# TK032F8004_TK499.net
KiCad netlist of a schematic drawn in Altium Designer
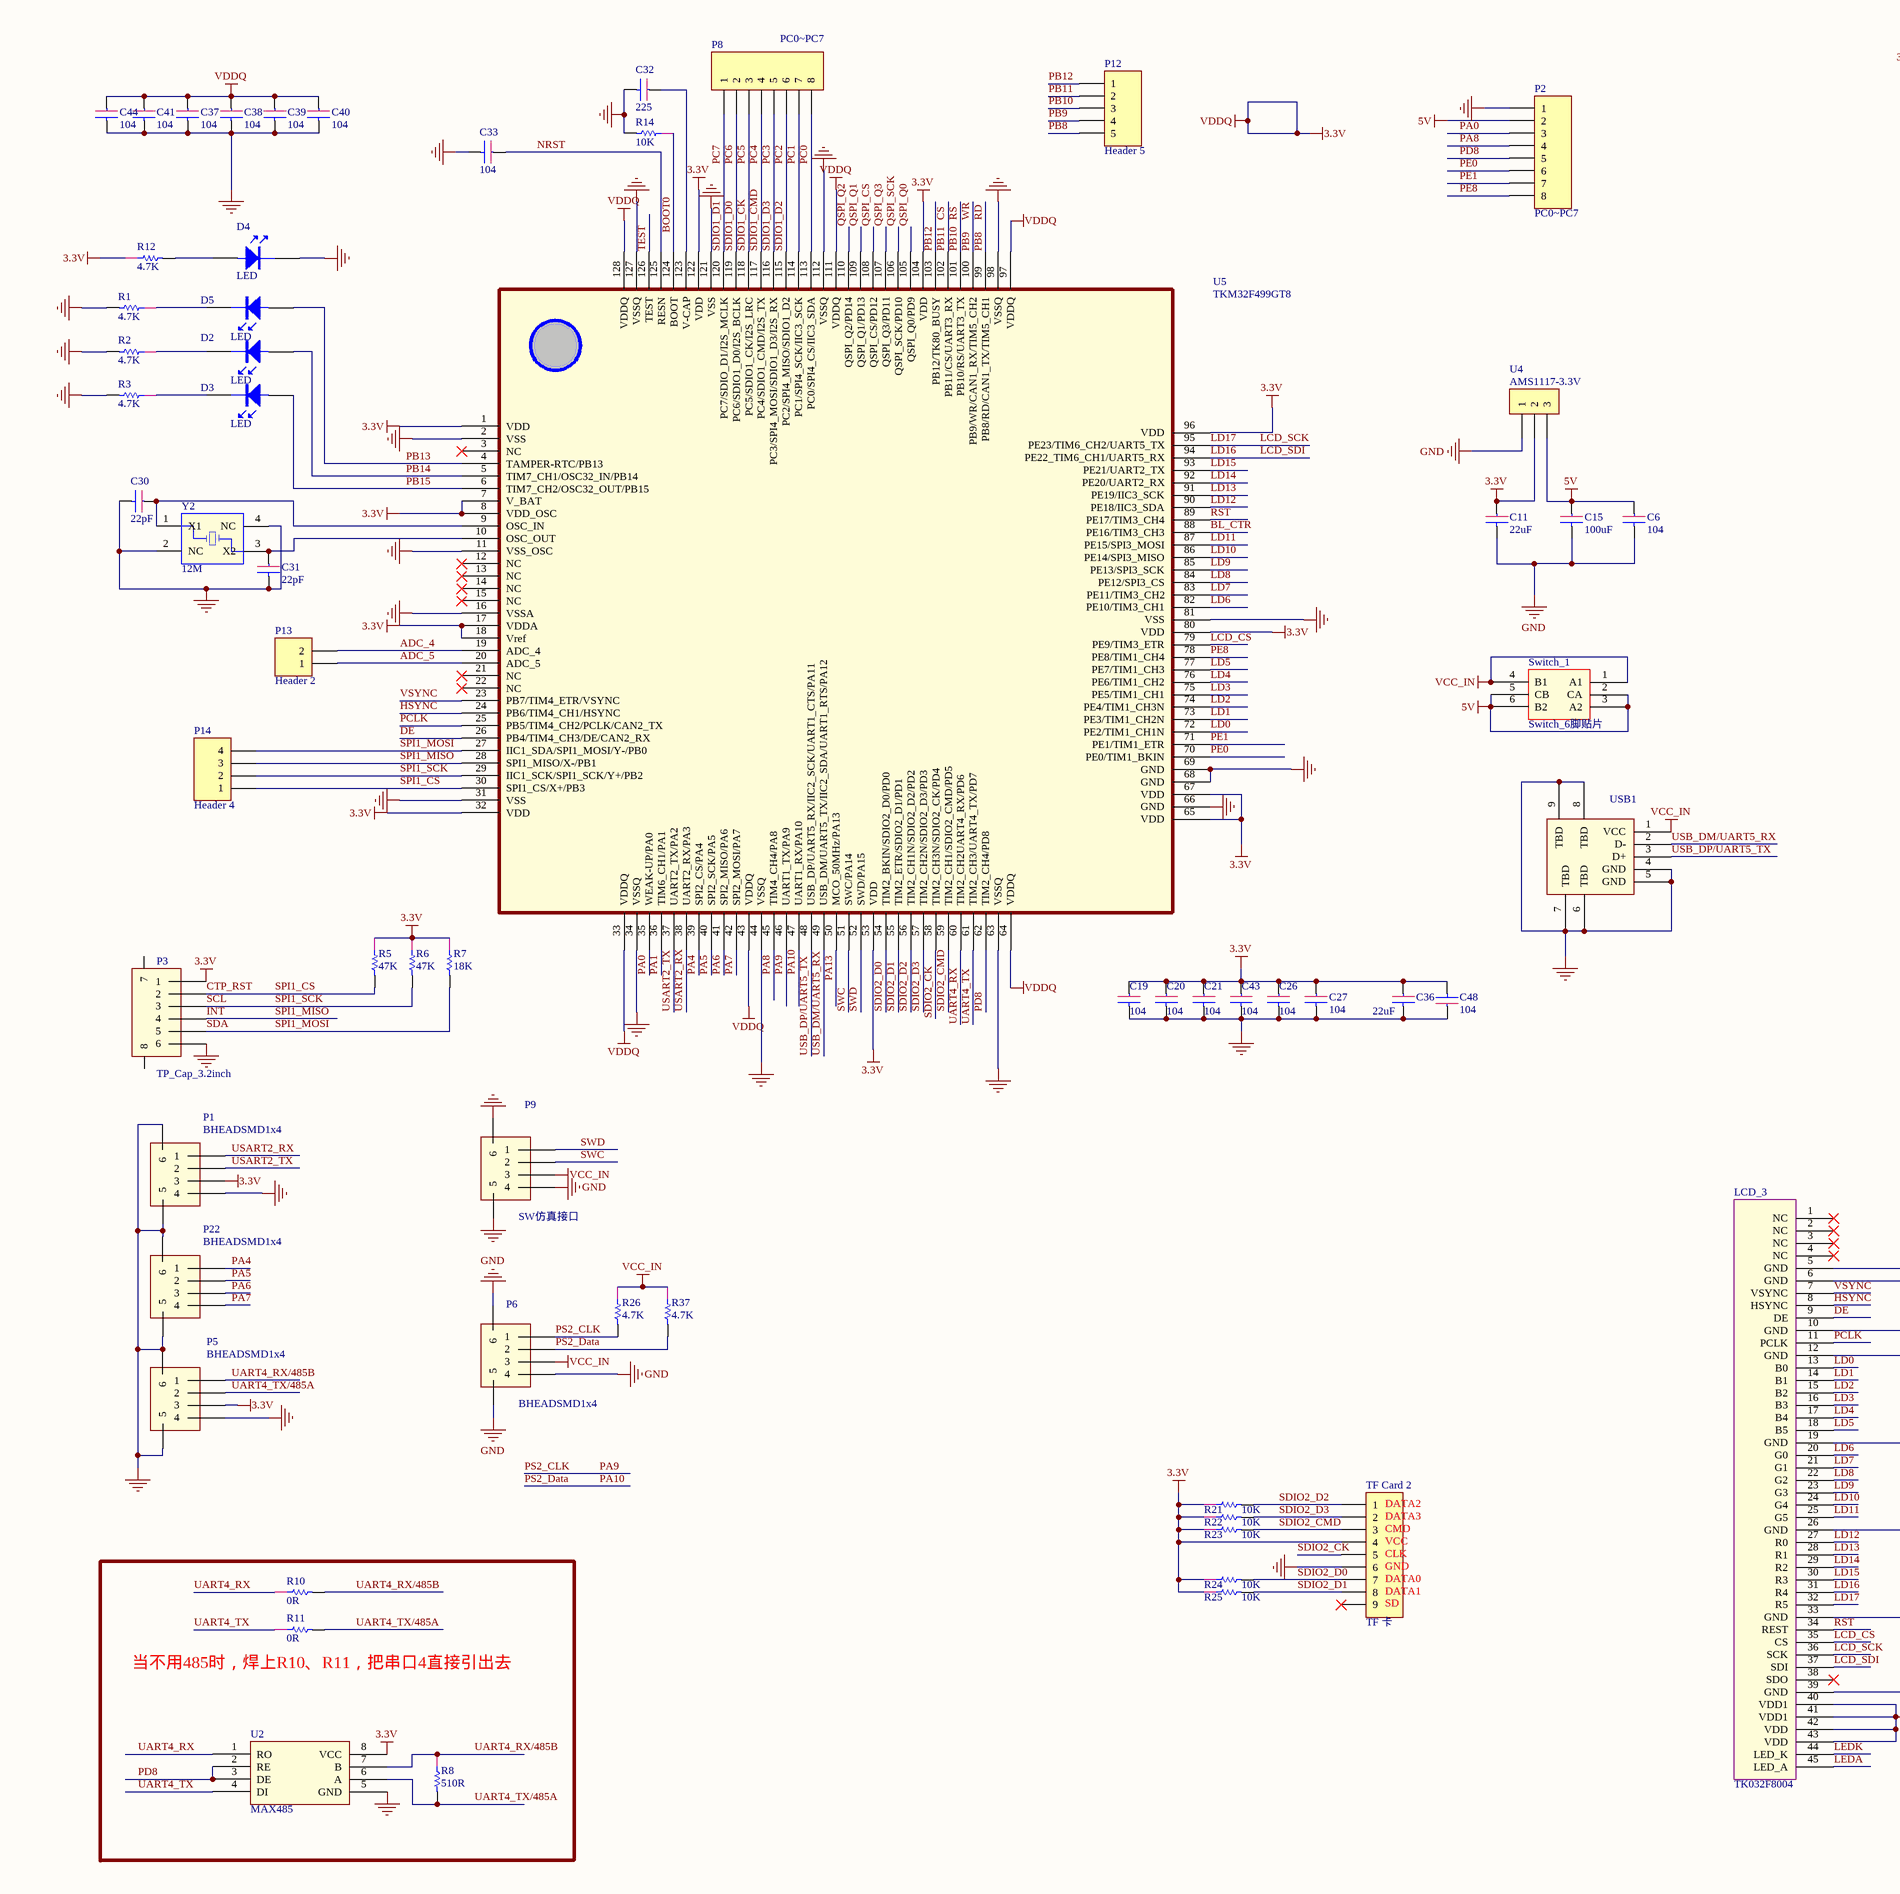
[diagram p0: TK032F8004_TK499.SchDoc, left]
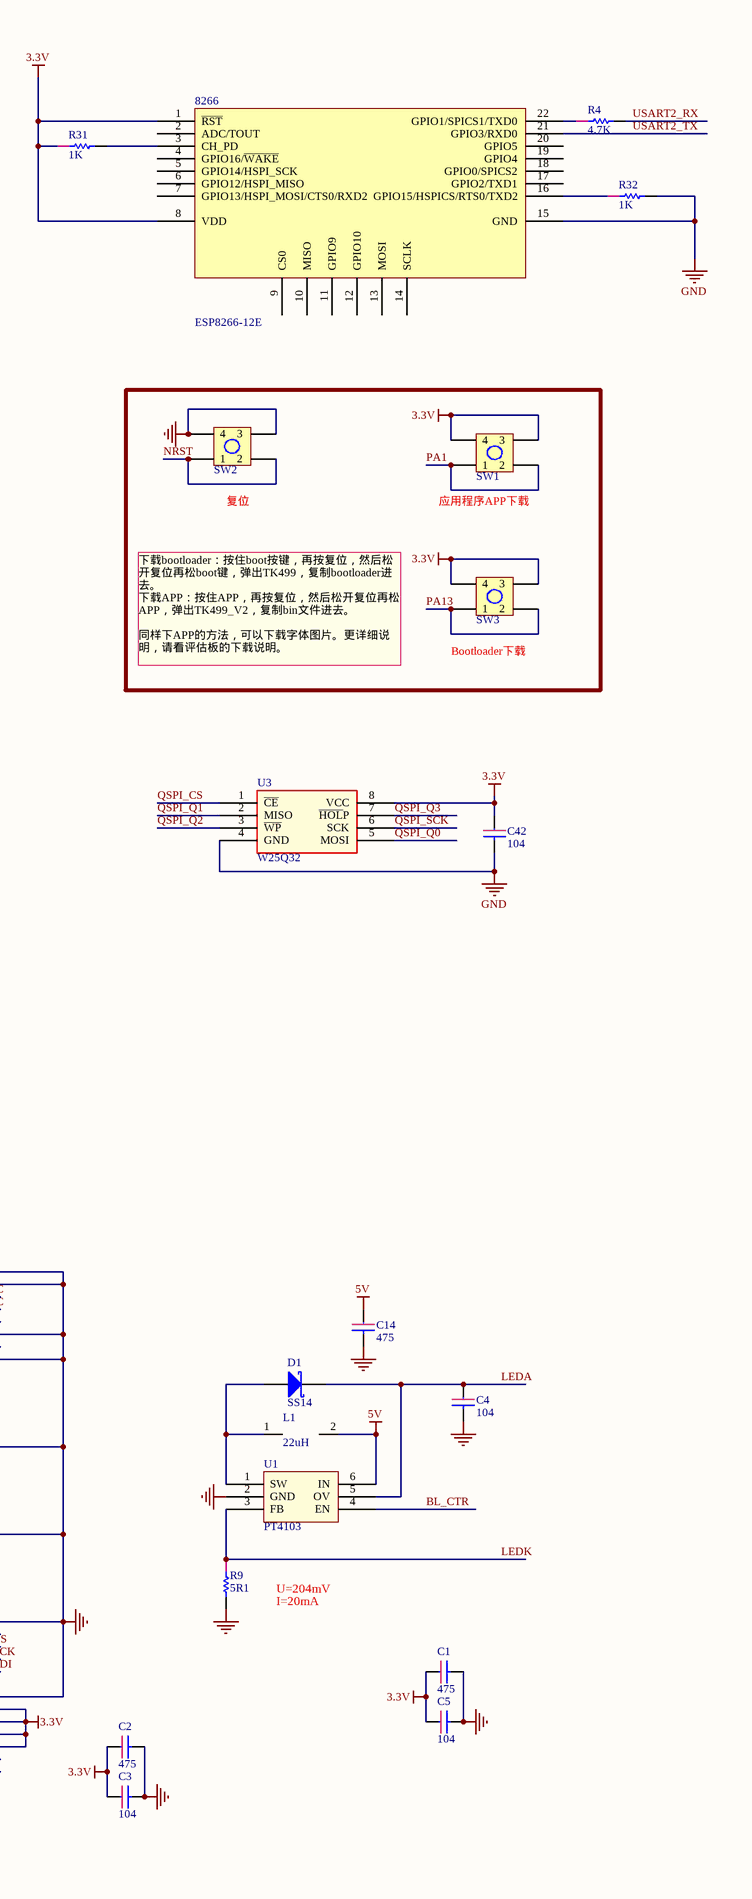
[diagram p1: TK032F8004_TK499.SchDoc, right]

(export (version "E")
  (design (tool "Eeschema 10.0.6"))
  (components
    (comp (ref "8266")
      (value "ESP8266-12E")
      (footprint "ESP8266-12E")
      (libsource (lib "Tiky") (part "ESP8266-12E"))
    )
    (comp (ref "C1") (value "475") (footprint "C0603-2") (libsource (lib "Tiky") (part "cap")))
    (comp (ref "C2") (value "475") (footprint "C0603-2") (libsource (lib "Tiky") (part "cap")))
    (comp (ref "C3") (value "104") (footprint "C0603-1") (libsource (lib "Tiky") (part "cap")))
    (comp (ref "C4") (value "104") (footprint "C0603-2") (libsource (lib "Tiky") (part "cap")))
    (comp (ref "C5") (value "104") (footprint "C0603-1") (libsource (lib "Tiky") (part "cap")))
    (comp (ref "C6") (value "104") (footprint "C0603-1") (libsource (lib "Tiky") (part "cap")))
    (comp (ref "C11") (value "22uF") (footprint "C0805-3") (libsource (lib "Tiky") (part "cap")))
    (comp (ref "C14") (value "475") (footprint "C0603-2") (libsource (lib "Tiky") (part "cap")))
    (comp (ref "C15") (value "100uF") (footprint "Case B 3528") (libsource (lib "Tiky") (part "cap")))
    (comp (ref "C19") (value "104") (footprint "C0603-1") (libsource (lib "Tiky") (part "cap")))
    (comp (ref "C20") (value "104") (footprint "C0603-1") (libsource (lib "Tiky") (part "cap")))
    (comp (ref "C21") (value "104") (footprint "C0603-1") (libsource (lib "Tiky") (part "cap")))
    (comp (ref "C26") (value "104") (footprint "C0603-1") (libsource (lib "Tiky") (part "cap")))
    (comp (ref "C27") (value "104") (footprint "C0603-2") (libsource (lib "Tiky") (part "cap")))
    (comp (ref "C30") (value "22pF") (footprint "C0603-1") (libsource (lib "Tiky") (part "cap")))
    (comp (ref "C31") (value "22pF") (footprint "C0603-1") (libsource (lib "Tiky") (part "cap")))
    (comp (ref "C32") (value "225") (footprint "C0603-2") (libsource (lib "Tiky") (part "cap")))
    (comp (ref "C33") (value "104") (footprint "C0603-1") (libsource (lib "Tiky") (part "cap")))
    (comp (ref "C36") (value "22uF") (footprint "C0805-3") (libsource (lib "Tiky") (part "cap")))
    (comp (ref "C37") (value "104") (footprint "C0603-1") (libsource (lib "Tiky") (part "cap")))
    (comp (ref "C38") (value "104") (footprint "C0603-1") (libsource (lib "Tiky") (part "cap")))
    (comp (ref "C39") (value "104") (footprint "C0603-1") (libsource (lib "Tiky") (part "cap")))
    (comp (ref "C40") (value "104") (footprint "C0603-1") (libsource (lib "Tiky") (part "cap")))
    (comp (ref "C41") (value "104") (footprint "C0603-1") (libsource (lib "Tiky") (part "cap")))
    (comp (ref "C42") (value "104") (footprint "C0603-1") (libsource (lib "Tiky") (part "cap")))
    (comp (ref "C43") (value "104") (footprint "C0603-1") (libsource (lib "Tiky") (part "cap")))
    (comp (ref "C44") (value "104") (footprint "C0603-1") (libsource (lib "Tiky") (part "cap")))
    (comp (ref "C48") (value "104") (footprint "C0603-1") (libsource (lib "Tiky") (part "cap")))
    (comp (ref "D1")
      (value "SS14")
      (footprint "SOD123")
      (description "Schottky Diode")
      (fields (field (name "PUBLISHER") "Altium Limited"))
      (libsource (lib "Miscellaneous Devices") (part "D Schottky"))
    )
    (comp (ref "D2") (value "LED") (footprint "D0603") (libsource (lib "*") (part "LED")))
    (comp (ref "D3") (value "LED") (footprint "D0603") (libsource (lib "*") (part "LED")))
    (comp (ref "D4") (value "LED") (footprint "D0603") (libsource (lib "*") (part "LED")))
    (comp (ref "D5") (value "LED") (footprint "D0603") (libsource (lib "*") (part "LED")))
    (comp (ref "L1") (value "22uH") (footprint "L1206") (libsource (lib "Tiky") (part "Inductor")))
    (comp (ref "LCD_3")
      (value "TK032F8004")
      (footprint "TK032F8004")
      (libsource (lib "Tiky") (part "TK032F8004"))
    )
    (comp (ref "P1")
      (value "BHEADSMD1x4")
      (footprint "BHEADSMD1x4")
      (libsource (lib "Tiky") (part "BHEADSMD1x4"))
    )
    (comp (ref "P2")
      (value "PC0~PC7")
      (footprint "HDR1X8")
      (description "Header, 8-Pin")
      (fields (field (name "PUBLISHER") "Altium Limited"))
      (libsource (lib "Miscellaneous Connectors") (part "Header 8"))
    )
    (comp (ref "P3")
      (value "TP_Cap_3.2inch")
      (footprint "TK032F8004_CTP")
      (libsource (lib "Tiky") (part "BHEADSMD1x6"))
    )
    (comp (ref "P5")
      (value "BHEADSMD1x4")
      (footprint "BHEADSMD1x4")
      (libsource (lib "Tiky") (part "BHEADSMD1x4"))
    )
    (comp (ref "P6")
      (value "BHEADSMD1x4")
      (footprint "BHEADSMD1x4")
      (libsource (lib "Tiky") (part "BHEADSMD1x4"))
    )
    (comp (ref "P8")
      (value "PC0~PC7")
      (footprint "HDR1X8")
      (description "Header, 8-Pin")
      (fields (field (name "PUBLISHER") "Altium Limited"))
      (libsource (lib "") (part "Header 8_1"))
    )
    (comp (ref "P9") (value "SW仿真接口") (footprint "BHEADSMD1x4") (libsource (lib "Tiky") (part "BHEADSMD1x4")))
    (comp (ref "P12")
      (value "Header 5")
      (footprint "HDR1X5")
      (description "Header, 5-Pin")
      (fields (field (name "PUBLISHER") "Altium Limited"))
      (libsource (lib "Miscellaneous Connectors") (part "Header 5"))
    )
    (comp (ref "P13")
      (value "Header 2")
      (footprint "HDR1X2")
      (description "Header, 2-Pin")
      (fields (field (name "PUBLISHER") "Altium Limited"))
      (libsource (lib "Miscellaneous Connectors") (part "Header 2"))
    )
    (comp (ref "P14")
      (value "Header 4")
      (footprint "BHEADSMD1x4")
      (description "Header, 4-Pin")
      (fields (field (name "PUBLISHER") "Altium Limited"))
      (libsource (lib "Miscellaneous Connectors") (part "Header 4"))
    )
    (comp (ref "P22")
      (value "BHEADSMD1x4")
      (footprint "BHEADSMD1x4")
      (libsource (lib "Tiky") (part "BHEADSMD1x4"))
    )
    (comp (ref "R1") (value "4.7K") (footprint "R0603") (libsource (lib "Tiky") (part "Resistor")))
    (comp (ref "R2") (value "4.7K") (footprint "R0603") (libsource (lib "Tiky") (part "Resistor")))
    (comp (ref "R3") (value "4.7K") (footprint "R0603") (libsource (lib "Tiky") (part "Resistor")))
    (comp (ref "R4") (value "4.7K") (footprint "R0603") (libsource (lib "Tiky") (part "Resistor")))
    (comp (ref "R5") (value "47K") (footprint "R0603") (libsource (lib "Tiky") (part "Resistor")))
    (comp (ref "R6") (value "47K") (footprint "R0603") (libsource (lib "Tiky") (part "Resistor")))
    (comp (ref "R7") (value "18K") (footprint "R0603") (libsource (lib "Tiky") (part "Resistor")))
    (comp (ref "R8") (value "510R") (footprint "R0603") (libsource (lib "Tiky") (part "Resistor")))
    (comp (ref "R9") (value "5R1") (footprint "R0603") (libsource (lib "Tiky") (part "Resistor")))
    (comp (ref "R10") (value "0R") (footprint "R0603") (libsource (lib "Tiky") (part "Resistor")))
    (comp (ref "R11") (value "0R") (footprint "R0603") (libsource (lib "Tiky") (part "Resistor")))
    (comp (ref "R12") (value "4.7K") (footprint "R0603") (libsource (lib "Tiky") (part "Resistor")))
    (comp (ref "R14") (value "10K") (footprint "R0603") (libsource (lib "Tiky") (part "Resistor")))
    (comp (ref "R21") (value "10K") (footprint "R0603") (libsource (lib "Tiky") (part "Resistor")))
    (comp (ref "R22") (value "10K") (footprint "R0603") (libsource (lib "Tiky") (part "Resistor")))
    (comp (ref "R23") (value "10K") (footprint "R0603") (libsource (lib "Tiky") (part "Resistor")))
    (comp (ref "R24") (value "10K") (footprint "R0603") (libsource (lib "Tiky") (part "Resistor")))
    (comp (ref "R25") (value "10K") (footprint "R0603") (libsource (lib "Tiky") (part "Resistor")))
    (comp (ref "R26") (value "4.7K") (footprint "R0603") (libsource (lib "Tiky") (part "Resistor")))
    (comp (ref "R31") (value "1K") (footprint "R0603") (libsource (lib "Tiky") (part "Resistor")))
    (comp (ref "R32") (value "1K") (footprint "R0603") (libsource (lib "Tiky") (part "Resistor")))
    (comp (ref "R37") (value "4.7K") (footprint "R0603") (libsource (lib "Tiky") (part "Resistor")))
    (comp (ref "SW1") (value "SW") (footprint "SW") (libsource (lib "Tiky") (part "SW")))
    (comp (ref "SW2") (value "SW") (footprint "SW") (libsource (lib "Tiky") (part "SW")))
    (comp (ref "SW3") (value "SW") (footprint "SW") (libsource (lib "Tiky") (part "SW")))
    (comp (ref "Switch_1")
      (value "Switch_6脚贴片")
      (footprint "Switch_6脚贴片")
      (libsource (lib "Tiky") (part "Switch_6脚贴片"))
    )
    (comp (ref "TF Card 2")
      (value "TF 卡")
      (footprint "Micro_SD")
      (description "Header, 9-Pin")
      (fields (field (name "PUBLISHER") "Altium Limited"))
      (libsource (lib "Miscellaneous Connectors") (part "Header 9"))
    )
    (comp (ref "U1") (value "PT4103") (footprint "SOT23-6") (libsource (lib "Tiky") (part "PT4101")))
    (comp (ref "U2") (value "MAX485") (footprint "SOP8-150") (libsource (lib "Tiky") (part "MAX485")))
    (comp (ref "U3") (value "W25Q32") (footprint "SOP8-215-50") (libsource (lib "Tiky") (part "W25Q16")))
    (comp (ref "U4")
      (value "AMS1117-3.3V")
      (footprint "SOT-223")
      (description "Connector")
      (libsource (lib "Miscellaneous Devices") (part "CON3"))
    )
    (comp (ref "U5")
      (value "TKM32F499GT8")
      (footprint "LQFP128")
      (libsource (lib "Tiky") (part "TKM32F499GT8"))
    )
    (comp (ref "USB1")
      (value "Micro USB")
      (footprint "MicroUSB_带定位柱")
      (libsource (lib "Tiky") (part "Mini USB"))
    )
    (comp (ref "Y2") (value "12M") (footprint "X3225") (libsource (lib "Tiky") (part "晶振_无源_4PIN_SMD")))
  )
  (nets
    (net (code "1") (name "/ADC_4") (class "Default")
      (node (ref "P13") (pin "2") (pinfunction "2_2") (pintype "passive"))
      (node (ref "U5") (pin "19") (pinfunction "ADC_4_19") (pintype "passive"))
    )
    (net (code "2") (name "/ADC_5") (class "Default")
      (node (ref "P13") (pin "1") (pinfunction "1_1") (pintype "passive"))
      (node (ref "U5") (pin "20") (pinfunction "ADC_5_20") (pintype "passive"))
    )
    (net (code "3") (name "/BL_CTR") (class "Default")
      (node (ref "U1") (pin "4") (pinfunction "EN_4") (pintype "passive"))
      (node (ref "U5") (pin "88") (pinfunction "PE16/TIM3_CH3_88") (pintype "passive"))
    )
    (net (code "4") (name "/BOOT0") (class "Default")
      (node (ref "R14") (pin "1") (pinfunction "1_1") (pintype "passive"))
      (node (ref "U5") (pin "124") (pinfunction "BOOT_124") (pintype "passive"))
    )
    (net (code "5") (name "/CS") (class "Default")
      (node (ref "P12") (pin "2") (pinfunction "2_2") (pintype "passive"))
      (node (ref "U5") (pin "102") (pinfunction "PB11/CS/UART3_RX_102") (pintype "passive"))
    )
    (net (code "6") (name "/CTP_RST") (class "Default")
      (node (ref "P14") (pin "1") (pinfunction "1_1") (pintype "passive"))
      (node (ref "P3") (pin "2") (pinfunction "2_2") (pintype "passive"))
      (node (ref "R5") (pin "2") (pinfunction "2_2") (pintype "passive"))
      (node (ref "U5") (pin "30") (pinfunction "SPI1_CS/X+/PB3_30") (pintype "passive"))
    )
    (net (code "7") (name "/DE") (class "Default")
      (node (ref "LCD_3") (pin "9") (pinfunction "DE_9") (pintype "passive"))
      (node (ref "U5") (pin "26") (pinfunction "PB4/TIM4_CH3/DE/CAN2_RX_26") (pintype "passive"))
    )
    (net (code "8") (name "/HSYNC") (class "Default")
      (node (ref "LCD_3") (pin "8") (pinfunction "HSYNC_8") (pintype "passive"))
      (node (ref "U5") (pin "24") (pinfunction "PB6/TIM4_CH1/HSYNC_24") (pintype "passive"))
    )
    (net (code "9") (name "/INT") (class "Default")
      (node (ref "P14") (pin "3") (pinfunction "3_3") (pintype "passive"))
      (node (ref "P3") (pin "4") (pinfunction "4_4") (pintype "passive"))
      (node (ref "U5") (pin "28") (pinfunction "SPI1_MISO/X-/PB1_28") (pintype "passive"))
    )
    (net (code "10") (name "/LCD_CS") (class "Default")
      (node (ref "LCD_3") (pin "35") (pinfunction "CS_35") (pintype "passive"))
      (node (ref "U5") (pin "79") (pinfunction "PE9/TIM3_ETR_79") (pintype "passive"))
    )
    (net (code "11") (name "/LCD_SCK") (class "Default")
      (node (ref "LCD_3") (pin "32") (pinfunction "R5_32") (pintype "passive"))
      (node (ref "LCD_3") (pin "36") (pinfunction "SCK_36") (pintype "passive"))
      (node (ref "U5") (pin "95") (pinfunction "PE23/TIM6_CH2/UART5_TX_95") (pintype "passive"))
    )
    (net (code "12") (name "/LCD_SDI") (class "Default")
      (node (ref "LCD_3") (pin "31") (pinfunction "R4_31") (pintype "passive"))
      (node (ref "LCD_3") (pin "37") (pinfunction "SDI_37") (pintype "passive"))
      (node (ref "U5") (pin "94") (pinfunction "PE22_TIM6_CH1/UART5_RX_94") (pintype "passive"))
    )
    (net (code "13") (name "/LD0") (class "Default")
      (node (ref "LCD_3") (pin "13") (pinfunction "B0_13") (pintype "passive"))
      (node (ref "U5") (pin "72") (pinfunction "PE2/TIM1_CH1N_72") (pintype "passive"))
    )
    (net (code "14") (name "/LD1") (class "Default")
      (node (ref "LCD_3") (pin "14") (pinfunction "B1_14") (pintype "passive"))
      (node (ref "U5") (pin "73") (pinfunction "PE3/TIM1_CH2N_73") (pintype "passive"))
    )
    (net (code "15") (name "/LD2") (class "Default")
      (node (ref "LCD_3") (pin "15") (pinfunction "B2_15") (pintype "passive"))
      (node (ref "U5") (pin "74") (pinfunction "PE4/TIM1_CH3N_74") (pintype "passive"))
    )
    (net (code "16") (name "/LD3") (class "Default")
      (node (ref "LCD_3") (pin "16") (pinfunction "B3_16") (pintype "passive"))
      (node (ref "U5") (pin "75") (pinfunction "PE5/TIM1_CH1_75") (pintype "passive"))
    )
    (net (code "17") (name "/LD4") (class "Default")
      (node (ref "LCD_3") (pin "17") (pinfunction "B4_17") (pintype "passive"))
      (node (ref "U5") (pin "76") (pinfunction "PE6/TIM1_CH2_76") (pintype "passive"))
    )
    (net (code "18") (name "/LD5") (class "Default")
      (node (ref "LCD_3") (pin "18") (pinfunction "B5_18") (pintype "passive"))
      (node (ref "U5") (pin "77") (pinfunction "PE7/TIM1_CH3_77") (pintype "passive"))
    )
    (net (code "19") (name "/LD6") (class "Default")
      (node (ref "LCD_3") (pin "20") (pinfunction "G0_20") (pintype "passive"))
      (node (ref "U5") (pin "82") (pinfunction "PE10/TIM3_CH1_82") (pintype "passive"))
    )
    (net (code "20") (name "/LD7") (class "Default")
      (node (ref "LCD_3") (pin "21") (pinfunction "G1_21") (pintype "passive"))
      (node (ref "U5") (pin "83") (pinfunction "PE11/TIM3_CH2_83") (pintype "passive"))
    )
    (net (code "21") (name "/LD8") (class "Default")
      (node (ref "LCD_3") (pin "22") (pinfunction "G2_22") (pintype "passive"))
      (node (ref "U5") (pin "84") (pinfunction "PE12/SPI3_CS_84") (pintype "passive"))
    )
    (net (code "22") (name "/LD9") (class "Default")
      (node (ref "LCD_3") (pin "23") (pinfunction "G3_23") (pintype "passive"))
      (node (ref "U5") (pin "85") (pinfunction "PE13/SPI3_SCK_85") (pintype "passive"))
    )
    (net (code "23") (name "/LD10") (class "Default")
      (node (ref "LCD_3") (pin "24") (pinfunction "G4_24") (pintype "passive"))
      (node (ref "U5") (pin "86") (pinfunction "PE14/SPI3_MISO_86") (pintype "passive"))
    )
    (net (code "24") (name "/LD11") (class "Default")
      (node (ref "LCD_3") (pin "25") (pinfunction "G5_25") (pintype "passive"))
      (node (ref "U5") (pin "87") (pinfunction "PE15/SPI3_MOSI_87") (pintype "passive"))
    )
    (net (code "25") (name "/LD12") (class "Default")
      (node (ref "LCD_3") (pin "27") (pinfunction "R0_27") (pintype "passive"))
      (node (ref "U5") (pin "90") (pinfunction "PE18/IIC3_SDA_90") (pintype "passive"))
    )
    (net (code "26") (name "/LD13") (class "Default")
      (node (ref "LCD_3") (pin "28") (pinfunction "R1_28") (pintype "passive"))
      (node (ref "U5") (pin "91") (pinfunction "PE19/IIC3_SCK_91") (pintype "passive"))
    )
    (net (code "27") (name "/LD14") (class "Default")
      (node (ref "LCD_3") (pin "29") (pinfunction "R2_29") (pintype "passive"))
      (node (ref "U5") (pin "92") (pinfunction "PE20/UART2_RX_92") (pintype "passive"))
    )
    (net (code "28") (name "/LD15") (class "Default")
      (node (ref "LCD_3") (pin "30") (pinfunction "R3_30") (pintype "passive"))
      (node (ref "U5") (pin "93") (pinfunction "PE21/UART2_TX_93") (pintype "passive"))
    )
    (net (code "29") (name "/LEDA") (class "Default")
      (node (ref "C4") (pin "1") (pinfunction "1_1") (pintype "passive"))
      (node (ref "D1") (pin "2") (pinfunction "K_2") (pintype "passive"))
      (node (ref "LCD_3") (pin "45") (pinfunction "LED_A_45") (pintype "passive"))
      (node (ref "U1") (pin "5") (pinfunction "OV_5") (pintype "passive"))
    )
    (net (code "30") (name "/LEDK") (class "Default")
      (node (ref "LCD_3") (pin "44") (pinfunction "LED_K_44") (pintype "passive"))
      (node (ref "R9") (pin "1") (pinfunction "1_1") (pintype "passive"))
      (node (ref "U1") (pin "3") (pinfunction "FB_3") (pintype "passive"))
    )
    (net (code "31") (name "/NRST") (class "Default")
      (node (ref "C33") (pin "1") (pinfunction "1_1") (pintype "passive"))
      (node (ref "SW2") (pin "1") (pinfunction "1_1") (pintype "passive"))
      (node (ref "SW2") (pin "2") (pinfunction "2_2") (pintype "passive"))
      (node (ref "U5") (pin "125") (pinfunction "RESN_125") (pintype "passive"))
    )
    (net (code "32") (name "/PA0") (class "Default")
      (node (ref "P2") (pin "3") (pinfunction "3_3") (pintype "passive"))
      (node (ref "U5") (pin "35") (pinfunction "WEAK-UP/PA0_35") (pintype "passive"))
    )
    (net (code "33") (name "/PA1") (class "Default")
      (node (ref "SW1") (pin "1") (pinfunction "1_1") (pintype "passive"))
      (node (ref "SW1") (pin "2") (pinfunction "2_2") (pintype "passive"))
      (node (ref "U5") (pin "36") (pinfunction "TIM6_CH1/PA1_36") (pintype "passive"))
    )
    (net (code "34") (name "/PA4") (class "Default")
      (node (ref "P22") (pin "1") (pinfunction "1_1") (pintype "passive"))
      (node (ref "U5") (pin "39") (pinfunction "SPI2_CS/PA4_39") (pintype "passive"))
    )
    (net (code "35") (name "/PA5") (class "Default")
      (node (ref "P22") (pin "2") (pinfunction "2_2") (pintype "passive"))
      (node (ref "U5") (pin "40") (pinfunction "SPI2_SCK/PA5_40") (pintype "passive"))
    )
    (net (code "36") (name "/PA6") (class "Default")
      (node (ref "P22") (pin "3") (pinfunction "3_3") (pintype "passive"))
      (node (ref "U5") (pin "41") (pinfunction "SPI2_MISO/PA6_41") (pintype "passive"))
    )
    (net (code "37") (name "/PA7") (class "Default")
      (node (ref "P22") (pin "4") (pinfunction "4_4") (pintype "passive"))
      (node (ref "U5") (pin "42") (pinfunction "SPI2_MOSI/PA7_42") (pintype "passive"))
    )
    (net (code "38") (name "/PA8") (class "Default")
      (node (ref "P2") (pin "4") (pinfunction "4_4") (pintype "passive"))
      (node (ref "U5") (pin "45") (pinfunction "TIM4_CH4/PA8_45") (pintype "passive"))
    )
    (net (code "39") (name "/PA9") (class "Default")
      (node (ref "P6") (pin "1") (pinfunction "1_1") (pintype "passive"))
      (node (ref "R26") (pin "2") (pinfunction "2_2") (pintype "passive"))
      (node (ref "U5") (pin "46") (pinfunction "UART1_TX/PA9_46") (pintype "passive"))
    )
    (net (code "40") (name "/PA10") (class "Default")
      (node (ref "P6") (pin "2") (pinfunction "2_2") (pintype "passive"))
      (node (ref "R37") (pin "2") (pinfunction "2_2") (pintype "passive"))
      (node (ref "U5") (pin "47") (pinfunction "UART1_RX/PA10_47") (pintype "passive"))
    )
    (net (code "41") (name "/PA13") (class "Default")
      (node (ref "SW3") (pin "1") (pinfunction "1_1") (pintype "passive"))
      (node (ref "SW3") (pin "2") (pinfunction "2_2") (pintype "passive"))
      (node (ref "U5") (pin "50") (pinfunction "MCO_50MHz/PA13_50") (pintype "passive"))
    )
    (net (code "42") (name "/PB8") (class "Default")
      (node (ref "P12") (pin "5") (pinfunction "5_5") (pintype "passive"))
      (node (ref "U5") (pin "99") (pinfunction "PB8/RD/CAN1_TX/TIM5_CH1_99") (pintype "passive"))
    )
    (net (code "43") (name "/PB9") (class "Default")
      (node (ref "P12") (pin "4") (pinfunction "4_4") (pintype "passive"))
      (node (ref "U5") (pin "100") (pinfunction "PB9/WR/CAN1_RX/TIM5_CH2_100") (pintype "passive"))
    )
    (net (code "44") (name "/PB10") (class "Default")
      (node (ref "P12") (pin "3") (pinfunction "3_3") (pintype "passive"))
      (node (ref "U5") (pin "101") (pinfunction "PB10/RS/UART3_TX_101") (pintype "passive"))
    )
    (net (code "45") (name "/PB12") (class "Default")
      (node (ref "P12") (pin "1") (pinfunction "1_1") (pintype "passive"))
      (node (ref "U5") (pin "103") (pinfunction "PB12/TK80_BUSY_103") (pintype "passive"))
    )
    (net (code "46") (name "/PB13") (class "Default")
      (node (ref "D5") (pin "1") (pinfunction "1_1") (pintype "passive"))
      (node (ref "U5") (pin "4") (pinfunction "TAMPER-RTC/PB13_4") (pintype "passive"))
    )
    (net (code "47") (name "/PB14") (class "Default")
      (node (ref "D2") (pin "1") (pinfunction "1_1") (pintype "passive"))
      (node (ref "U5") (pin "5") (pinfunction "TIM7_CH1/OSC32_IN/PB14_5") (pintype "passive"))
    )
    (net (code "48") (name "/PB15") (class "Default")
      (node (ref "D3") (pin "1") (pinfunction "1_1") (pintype "passive"))
      (node (ref "U5") (pin "6") (pinfunction "TIM7_CH2/OSC32_OUT/PB15_6") (pintype "passive"))
    )
    (net (code "49") (name "/PC0") (class "Default")
      (node (ref "P8") (pin "8") (pinfunction "8_8") (pintype "passive"))
      (node (ref "U5") (pin "113") (pinfunction "PC0/SPI4_CS/IIC3_SDA_113") (pintype "passive"))
    )
    (net (code "50") (name "/PC1") (class "Default")
      (node (ref "P8") (pin "7") (pinfunction "7_7") (pintype "passive"))
      (node (ref "U5") (pin "114") (pinfunction "PC1/SPI4_SCK/IIC3_SCK_114") (pintype "passive"))
    )
    (net (code "51") (name "/PC2") (class "Default")
      (node (ref "P8") (pin "6") (pinfunction "6_6") (pintype "passive"))
      (node (ref "U5") (pin "115") (pinfunction "PC2/SPI4_MISO/SDIO1_D2_115") (pintype "passive"))
    )
    (net (code "52") (name "/PC3") (class "Default")
      (node (ref "P8") (pin "5") (pinfunction "5_5") (pintype "passive"))
      (node (ref "U5") (pin "116") (pinfunction "PC3/SPI4_MOSI/SDIO1_D3/I2S_RX_116") (pintype "passive"))
    )
    (net (code "53") (name "/PC4") (class "Default")
      (node (ref "P8") (pin "4") (pinfunction "4_4") (pintype "passive"))
      (node (ref "U5") (pin "117") (pinfunction "PC4/SDIO1_CMD/I2S_TX_117") (pintype "passive"))
    )
    (net (code "54") (name "/PC5") (class "Default")
      (node (ref "P8") (pin "3") (pinfunction "3_3") (pintype "passive"))
      (node (ref "U5") (pin "118") (pinfunction "PC5/SDIO1_CK/I2S_LRC_118") (pintype "passive"))
    )
    (net (code "55") (name "/PC6") (class "Default")
      (node (ref "P8") (pin "2") (pinfunction "2_2") (pintype "passive"))
      (node (ref "U5") (pin "119") (pinfunction "PC6/SDIO1_D0/I2S_BCLK_119") (pintype "passive"))
    )
    (net (code "56") (name "/PC7") (class "Default")
      (node (ref "P8") (pin "1") (pinfunction "1_1") (pintype "passive"))
      (node (ref "U5") (pin "120") (pinfunction "PC7/SDIO_D1/I2S_MCLK_120") (pintype "passive"))
    )
    (net (code "57") (name "/PCLK") (class "Default")
      (node (ref "LCD_3") (pin "11") (pinfunction "PCLK_11") (pintype "passive"))
      (node (ref "U5") (pin "25") (pinfunction "PB5/TIM4_CH2/PCLK/CAN2_TX_25") (pintype "passive"))
    )
    (net (code "58") (name "/PD8") (class "Default")
      (node (ref "P2") (pin "5") (pinfunction "5_5") (pintype "passive"))
      (node (ref "U2") (pin "2") (pinfunction "RE_2") (pintype "passive"))
      (node (ref "U2") (pin "3") (pinfunction "DE_3") (pintype "passive"))
      (node (ref "U5") (pin "62") (pinfunction "TIM2_CH4/PD8_62") (pintype "passive"))
    )
    (net (code "59") (name "/PE0") (class "Default")
      (node (ref "P2") (pin "6") (pinfunction "6_6") (pintype "passive"))
      (node (ref "U5") (pin "70") (pinfunction "PE0/TIM1_BKIN_70") (pintype "passive"))
    )
    (net (code "60") (name "/PE1") (class "Default")
      (node (ref "P2") (pin "7") (pinfunction "7_7") (pintype "passive"))
      (node (ref "U5") (pin "71") (pinfunction "PE1/TIM1_ETR_71") (pintype "passive"))
    )
    (net (code "61") (name "/PE8") (class "Default")
      (node (ref "P2") (pin "8") (pinfunction "8_8") (pintype "passive"))
      (node (ref "U5") (pin "78") (pinfunction "PE8/TIM1_CH4_78") (pintype "passive"))
    )
    (net (code "62") (name "/QSPI_CS") (class "Default")
      (node (ref "U3") (pin "1") (pinfunction "~{CE}_1") (pintype "passive"))
      (node (ref "U5") (pin "108") (pinfunction "QSPI_CS/PD12_108") (pintype "passive"))
    )
    (net (code "63") (name "/QSPI_Q0") (class "Default")
      (node (ref "U3") (pin "5") (pinfunction "MOSI_5") (pintype "passive"))
      (node (ref "U5") (pin "105") (pinfunction "QSPI_Q0/PD9_105") (pintype "passive"))
    )
    (net (code "64") (name "/QSPI_Q1") (class "Default")
      (node (ref "U3") (pin "2") (pinfunction "MISO_2") (pintype "passive"))
      (node (ref "U5") (pin "109") (pinfunction "QSPI_Q1/PD13_109") (pintype "passive"))
    )
    (net (code "65") (name "/QSPI_Q2") (class "Default")
      (node (ref "U3") (pin "3") (pinfunction "~{WP}_3") (pintype "passive"))
      (node (ref "U5") (pin "110") (pinfunction "QSPI_Q2/PD14_110") (pintype "passive"))
    )
    (net (code "66") (name "/QSPI_Q3") (class "Default")
      (node (ref "U3") (pin "7") (pinfunction "~{HOL}P_7") (pintype "passive"))
      (node (ref "U5") (pin "107") (pinfunction "QSPI_Q3/PD11_107") (pintype "passive"))
    )
    (net (code "67") (name "/QSPI_SCK") (class "Default")
      (node (ref "U3") (pin "6") (pinfunction "SCK_6") (pintype "passive"))
      (node (ref "U5") (pin "106") (pinfunction "QSPI_SCK/PD10_106") (pintype "passive"))
    )
    (net (code "68") (name "/RST") (class "Default")
      (node (ref "LCD_3") (pin "34") (pinfunction "REST_34") (pintype "passive"))
      (node (ref "U5") (pin "89") (pinfunction "PE17/TIM3_CH4_89") (pintype "passive"))
    )
    (net (code "69") (name "/SCL") (class "Default")
      (node (ref "P14") (pin "2") (pinfunction "2_2") (pintype "passive"))
      (node (ref "P3") (pin "3") (pinfunction "3_3") (pintype "passive"))
      (node (ref "R6") (pin "2") (pinfunction "2_2") (pintype "passive"))
      (node (ref "U5") (pin "29") (pinfunction "IIC1_SCK/SPI1_SCK/Y+/PB2_29") (pintype "passive"))
    )
    (net (code "70") (name "/SDA") (class "Default")
      (node (ref "P14") (pin "4") (pinfunction "4_4") (pintype "passive"))
      (node (ref "P3") (pin "5") (pinfunction "5_5") (pintype "passive"))
      (node (ref "R7") (pin "2") (pinfunction "2_2") (pintype "passive"))
      (node (ref "U5") (pin "27") (pinfunction "IIC1_SDA/SPI1_MOSI/Y-/PB0_27") (pintype "passive"))
    )
    (net (code "71") (name "/SDIO2_CK") (class "Default")
      (node (ref "TF Card 2") (pin "5") (pinfunction "5_5") (pintype "passive"))
      (node (ref "U5") (pin "58") (pinfunction "TIM2_CH3N/SDIO2_CK/PD4_58") (pintype "passive"))
    )
    (net (code "72") (name "/SDIO2_CMD") (class "Default")
      (node (ref "R23") (pin "2") (pinfunction "2_2") (pintype "passive"))
      (node (ref "TF Card 2") (pin "3") (pinfunction "3_3") (pintype "passive"))
      (node (ref "U5") (pin "59") (pinfunction "TIM2_CH1/SDIO2_CMD/PD5_59") (pintype "passive"))
    )
    (net (code "73") (name "/SDIO2_D0") (class "Default")
      (node (ref "R24") (pin "2") (pinfunction "2_2") (pintype "passive"))
      (node (ref "TF Card 2") (pin "7") (pinfunction "7_7") (pintype "passive"))
      (node (ref "U5") (pin "54") (pinfunction "TIM2_BKIN/SDIO2_D0/PD0_54") (pintype "passive"))
    )
    (net (code "74") (name "/SDIO2_D1") (class "Default")
      (node (ref "R25") (pin "2") (pinfunction "2_2") (pintype "passive"))
      (node (ref "TF Card 2") (pin "8") (pinfunction "8_8") (pintype "passive"))
      (node (ref "U5") (pin "55") (pinfunction "TIM2_ETR/SDIO2_D1/PD1_55") (pintype "passive"))
    )
    (net (code "75") (name "/SDIO2_D2") (class "Default")
      (node (ref "R21") (pin "2") (pinfunction "2_2") (pintype "passive"))
      (node (ref "TF Card 2") (pin "1") (pinfunction "1_1") (pintype "passive"))
      (node (ref "U5") (pin "56") (pinfunction "TIM2_CH1N/SDIO2_D2/PD2_56") (pintype "passive"))
    )
    (net (code "76") (name "/SDIO2_D3") (class "Default")
      (node (ref "R22") (pin "2") (pinfunction "2_2") (pintype "passive"))
      (node (ref "TF Card 2") (pin "2") (pinfunction "2_2") (pintype "passive"))
      (node (ref "U5") (pin "57") (pinfunction "TIM2_CH2N/SDIO2_D3/PD3_57") (pintype "passive"))
    )
    (net (code "77") (name "/SWC") (class "Default")
      (node (ref "P9") (pin "2") (pinfunction "2_2") (pintype "passive"))
      (node (ref "U5") (pin "51") (pinfunction "SWC/PA14_51") (pintype "passive"))
    )
    (net (code "78") (name "/SWD") (class "Default")
      (node (ref "P9") (pin "1") (pinfunction "1_1") (pintype "passive"))
      (node (ref "U5") (pin "52") (pinfunction "SWD/PA15_52") (pintype "passive"))
    )
    (net (code "79") (name "/TEST") (class "Default")
      (node (ref "U5") (pin "126") (pinfunction "TEST_126") (pintype "passive"))
    )
    (net (code "80") (name "/UART4_RX") (class "Default")
      (node (ref "R10") (pin "1") (pinfunction "1_1") (pintype "passive"))
      (node (ref "U2") (pin "1") (pinfunction "RO_1") (pintype "passive"))
      (node (ref "U5") (pin "60") (pinfunction "TIM2_CH2UART4_RX/PD6_60") (pintype "passive"))
    )
    (net (code "81") (name "/UART4_RX{slash}485B") (class "Default")
      (node (ref "P5") (pin "1") (pinfunction "1_1") (pintype "passive"))
      (node (ref "R10") (pin "2") (pinfunction "2_2") (pintype "passive"))
      (node (ref "R8") (pin "1") (pinfunction "1_1") (pintype "passive"))
      (node (ref "U2") (pin "7") (pinfunction "B_7") (pintype "passive"))
    )
    (net (code "82") (name "/UART4_TX") (class "Default")
      (node (ref "R11") (pin "1") (pinfunction "1_1") (pintype "passive"))
      (node (ref "U2") (pin "4") (pinfunction "DI_4") (pintype "passive"))
      (node (ref "U5") (pin "61") (pinfunction "TIM2_CH3/UART4_TX/PD7_61") (pintype "passive"))
    )
    (net (code "83") (name "/UART4_TX{slash}485A") (class "Default")
      (node (ref "P5") (pin "2") (pinfunction "2_2") (pintype "passive"))
      (node (ref "R11") (pin "2") (pinfunction "2_2") (pintype "passive"))
      (node (ref "R8") (pin "2") (pinfunction "2_2") (pintype "passive"))
      (node (ref "U2") (pin "6") (pinfunction "A_6") (pintype "passive"))
    )
    (net (code "84") (name "/USART2_RX") (class "Default")
      (node (ref "P1") (pin "1") (pinfunction "1_1") (pintype "passive"))
      (node (ref "R4") (pin "2") (pinfunction "2_2") (pintype "passive"))
      (node (ref "U5") (pin "38") (pinfunction "UART2_RX/PA3_38") (pintype "passive"))
    )
    (net (code "85") (name "/USART2_TX") (class "Default")
      (node (ref "8266") (pin "21") (pinfunction "GPIO3/RXD0_21") (pintype "passive"))
      (node (ref "P1") (pin "2") (pinfunction "2_2") (pintype "passive"))
      (node (ref "U5") (pin "37") (pinfunction "UART2_TX/PA2_37") (pintype "passive"))
    )
    (net (code "86") (name "/USB_DM{slash}UART5_RX") (class "Default")
      (node (ref "U5") (pin "49") (pinfunction "USB_DM/UART5_TX/IIC2_SDA/UART1_RTS/PA12_49") (pintype "passive"))
      (node (ref "USB1") (pin "2") (pinfunction "D-_2") (pintype "passive"))
    )
    (net (code "87") (name "/USB_DP{slash}UART5_TX") (class "Default")
      (node (ref "U5") (pin "48") (pinfunction "USB_DP/UART5_RX/IIC2_SCK/UART1_CTS/PA11_48") (pintype "passive"))
      (node (ref "USB1") (pin "3") (pinfunction "D+_3") (pintype "passive"))
    )
    (net (code "88") (name "/VSYNC") (class "Default")
      (node (ref "LCD_3") (pin "7") (pinfunction "VSYNC_7") (pintype "passive"))
      (node (ref "U5") (pin "23") (pinfunction "PB7/TIM4_ETR/VSYNC_23") (pintype "passive"))
    )
    (net (code "89") (name "3.3V") (class "Default")
      (node (ref "8266") (pin "1") (pinfunction "~{RST}_1") (pintype "passive"))
      (node (ref "8266") (pin "8") (pinfunction "VDD_8") (pintype "passive"))
      (node (ref "C1") (pin "1") (pinfunction "1_1") (pintype "passive"))
      (node (ref "C11") (pin "1") (pinfunction "1_1") (pintype "passive"))
      (node (ref "C19") (pin "1") (pinfunction "1_1") (pintype "passive"))
      (node (ref "C2") (pin "1") (pinfunction "1_1") (pintype "passive"))
      (node (ref "C20") (pin "1") (pinfunction "1_1") (pintype "passive"))
      (node (ref "C21") (pin "1") (pinfunction "1_1") (pintype "passive"))
      (node (ref "C26") (pin "1") (pinfunction "1_1") (pintype "passive"))
      (node (ref "C27") (pin "1") (pinfunction "1_1") (pintype "passive"))
      (node (ref "C3") (pin "1") (pinfunction "1_1") (pintype "passive"))
      (node (ref "C36") (pin "1") (pinfunction "1_1") (pintype "passive"))
      (node (ref "C37") (pin "1") (pinfunction "1_1") (pintype "passive"))
      (node (ref "C38") (pin "1") (pinfunction "1_1") (pintype "passive"))
      (node (ref "C39") (pin "1") (pinfunction "1_1") (pintype "passive"))
      (node (ref "C40") (pin "1") (pinfunction "1_1") (pintype "passive"))
      (node (ref "C41") (pin "1") (pinfunction "1_1") (pintype "passive"))
      (node (ref "C42") (pin "1") (pinfunction "1_1") (pintype "passive"))
      (node (ref "C43") (pin "1") (pinfunction "1_1") (pintype "passive"))
      (node (ref "C44") (pin "1") (pinfunction "1_1") (pintype "passive"))
      (node (ref "C48") (pin "2") (pinfunction "2_2") (pintype "passive"))
      (node (ref "C5") (pin "1") (pinfunction "1_1") (pintype "passive"))
      (node (ref "LCD_3") (pin "40") (pinfunction "VDD1_40") (pintype "passive"))
      (node (ref "LCD_3") (pin "41") (pinfunction "VDD1_41") (pintype "passive"))
      (node (ref "LCD_3") (pin "42") (pinfunction "VDD_42") (pintype "passive"))
      (node (ref "LCD_3") (pin "43") (pinfunction "VDD_43") (pintype "passive"))
      (node (ref "P1") (pin "3") (pinfunction "3_3") (pintype "passive"))
      (node (ref "P3") (pin "1") (pinfunction "1_1") (pintype "passive"))
      (node (ref "P5") (pin "3") (pinfunction "3_3") (pintype "passive"))
      (node (ref "R12") (pin "1") (pinfunction "1_1") (pintype "passive"))
      (node (ref "R21") (pin "1") (pinfunction "1_1") (pintype "passive"))
      (node (ref "R22") (pin "1") (pinfunction "1_1") (pintype "passive"))
      (node (ref "R23") (pin "1") (pinfunction "1_1") (pintype "passive"))
      (node (ref "R24") (pin "1") (pinfunction "1_1") (pintype "passive"))
      (node (ref "R25") (pin "1") (pinfunction "1_1") (pintype "passive"))
      (node (ref "R31") (pin "1") (pinfunction "1_1") (pintype "passive"))
      (node (ref "R5") (pin "1") (pinfunction "1_1") (pintype "passive"))
      (node (ref "R6") (pin "1") (pinfunction "1_1") (pintype "passive"))
      (node (ref "R7") (pin "1") (pinfunction "1_1") (pintype "passive"))
      (node (ref "SW1") (pin "3") (pinfunction "3_3") (pintype "passive"))
      (node (ref "SW1") (pin "4") (pinfunction "4_4") (pintype "passive"))
      (node (ref "SW3") (pin "3") (pinfunction "3_3") (pintype "passive"))
      (node (ref "SW3") (pin "4") (pinfunction "4_4") (pintype "passive"))
      (node (ref "TF Card 2") (pin "4") (pinfunction "4_4") (pintype "passive"))
      (node (ref "U2") (pin "8") (pinfunction "VCC_8") (pintype "passive"))
      (node (ref "U3") (pin "8") (pinfunction "VCC_8") (pintype "passive"))
      (node (ref "U4") (pin "2") (pinfunction "2_2") (pintype "passive"))
      (node (ref "U5") (pin "1") (pinfunction "VDD_1") (pintype "passive"))
      (node (ref "U5") (pin "104") (pinfunction "VDD_104") (pintype "passive"))
      (node (ref "U5") (pin "111") (pinfunction "VDDQ_111") (pintype "passive"))
      (node (ref "U5") (pin "122") (pinfunction "VDD_122") (pintype "passive"))
      (node (ref "U5") (pin "128") (pinfunction "VDDQ_128") (pintype "passive"))
      (node (ref "U5") (pin "17") (pinfunction "VDDA_17") (pintype "passive"))
      (node (ref "U5") (pin "18") (pinfunction "Vref_18") (pintype "passive"))
      (node (ref "U5") (pin "32") (pinfunction "VDD_32") (pintype "passive"))
      (node (ref "U5") (pin "33") (pinfunction "VDDQ_33") (pintype "passive"))
      (node (ref "U5") (pin "43") (pinfunction "VDDQ_43") (pintype "passive"))
      (node (ref "U5") (pin "53") (pinfunction "VDD_53") (pintype "passive"))
      (node (ref "U5") (pin "64") (pinfunction "VDDQ_64") (pintype "passive"))
      (node (ref "U5") (pin "65") (pinfunction "VDD_65") (pintype "passive"))
      (node (ref "U5") (pin "67") (pinfunction "VDD_67") (pintype "passive"))
      (node (ref "U5") (pin "7") (pinfunction "V_BAT_7") (pintype "passive"))
      (node (ref "U5") (pin "8") (pinfunction "VDD_OSC_8") (pintype "passive"))
      (node (ref "U5") (pin "80") (pinfunction "VDD_80") (pintype "passive"))
      (node (ref "U5") (pin "96") (pinfunction "VDD_96") (pintype "passive"))
      (node (ref "U5") (pin "97") (pinfunction "VDDQ_97") (pintype "passive"))
    )
    (net (code "90") (name "5V") (class "Default")
      (node (ref "C14") (pin "1") (pinfunction "1_1") (pintype "passive"))
      (node (ref "C15") (pin "1") (pinfunction "1_1") (pintype "passive"))
      (node (ref "C6") (pin "1") (pinfunction "1_1") (pintype "passive"))
      (node (ref "L1") (pin "2") (pinfunction "2_2") (pintype "passive"))
      (node (ref "P2") (pin "2") (pinfunction "2_2") (pintype "passive"))
      (node (ref "Switch_1") (pin "2") (pinfunction "CA_2") (pintype "passive"))
      (node (ref "Switch_1") (pin "3") (pinfunction "A2_3") (pintype "passive"))
      (node (ref "Switch_1") (pin "5") (pinfunction "CB_5") (pintype "passive"))
      (node (ref "Switch_1") (pin "6") (pinfunction "B2_6") (pintype "passive"))
      (node (ref "U1") (pin "6") (pinfunction "IN_6") (pintype "passive"))
      (node (ref "U4") (pin "3") (pinfunction "3_3") (pintype "passive"))
    )
    (net (code "91") (name "GND") (class "Default")
      (node (ref "8266") (pin "15") (pinfunction "GND_15") (pintype "passive"))
      (node (ref "C1") (pin "2") (pinfunction "2_2") (pintype "passive"))
      (node (ref "C11") (pin "2") (pinfunction "2_2") (pintype "passive"))
      (node (ref "C14") (pin "2") (pinfunction "2_2") (pintype "passive"))
      (node (ref "C15") (pin "2") (pinfunction "2_2") (pintype "passive"))
      (node (ref "C19") (pin "2") (pinfunction "2_2") (pintype "passive"))
      (node (ref "C2") (pin "2") (pinfunction "2_2") (pintype "passive"))
      (node (ref "C20") (pin "2") (pinfunction "2_2") (pintype "passive"))
      (node (ref "C21") (pin "2") (pinfunction "2_2") (pintype "passive"))
      (node (ref "C26") (pin "2") (pinfunction "2_2") (pintype "passive"))
      (node (ref "C27") (pin "2") (pinfunction "2_2") (pintype "passive"))
      (node (ref "C3") (pin "2") (pinfunction "2_2") (pintype "passive"))
      (node (ref "C30") (pin "2") (pinfunction "2_2") (pintype "passive"))
      (node (ref "C31") (pin "2") (pinfunction "2_2") (pintype "passive"))
      (node (ref "C32") (pin "2") (pinfunction "2_2") (pintype "passive"))
      (node (ref "C33") (pin "2") (pinfunction "2_2") (pintype "passive"))
      (node (ref "C36") (pin "2") (pinfunction "2_2") (pintype "passive"))
      (node (ref "C37") (pin "2") (pinfunction "2_2") (pintype "passive"))
      (node (ref "C38") (pin "2") (pinfunction "2_2") (pintype "passive"))
      (node (ref "C39") (pin "2") (pinfunction "2_2") (pintype "passive"))
      (node (ref "C4") (pin "2") (pinfunction "2_2") (pintype "passive"))
      (node (ref "C40") (pin "2") (pinfunction "2_2") (pintype "passive"))
      (node (ref "C41") (pin "2") (pinfunction "2_2") (pintype "passive"))
      (node (ref "C42") (pin "2") (pinfunction "2_2") (pintype "passive"))
      (node (ref "C43") (pin "2") (pinfunction "2_2") (pintype "passive"))
      (node (ref "C44") (pin "2") (pinfunction "2_2") (pintype "passive"))
      (node (ref "C48") (pin "1") (pinfunction "1_1") (pintype "passive"))
      (node (ref "C5") (pin "2") (pinfunction "2_2") (pintype "passive"))
      (node (ref "C6") (pin "2") (pinfunction "2_2") (pintype "passive"))
      (node (ref "D4") (pin "2") (pinfunction "2_2") (pintype "passive"))
      (node (ref "LCD_3") (pin "10") (pinfunction "GND_10") (pintype "passive"))
      (node (ref "LCD_3") (pin "12") (pinfunction "GND_12") (pintype "passive"))
      (node (ref "LCD_3") (pin "19") (pinfunction "GND_19") (pintype "passive"))
      (node (ref "LCD_3") (pin "26") (pinfunction "GND_26") (pintype "passive"))
      (node (ref "LCD_3") (pin "33") (pinfunction "GND_33") (pintype "passive"))
      (node (ref "LCD_3") (pin "39") (pinfunction "GND_39") (pintype "passive"))
      (node (ref "LCD_3") (pin "5") (pinfunction "GND_5") (pintype "passive"))
      (node (ref "LCD_3") (pin "6") (pinfunction "GND_6") (pintype "passive"))
      (node (ref "P1") (pin "4") (pinfunction "4_4") (pintype "passive"))
      (node (ref "P1") (pin "5") (pinfunction "5_5") (pintype "passive"))
      (node (ref "P1") (pin "6") (pinfunction "6_6") (pintype "passive"))
      (node (ref "P2") (pin "1") (pinfunction "1_1") (pintype "passive"))
      (node (ref "P22") (pin "5") (pinfunction "5_5") (pintype "passive"))
      (node (ref "P22") (pin "6") (pinfunction "6_6") (pintype "passive"))
      (node (ref "P3") (pin "6") (pinfunction "6_6") (pintype "passive"))
      (node (ref "P5") (pin "4") (pinfunction "4_4") (pintype "passive"))
      (node (ref "P5") (pin "5") (pinfunction "5_5") (pintype "passive"))
      (node (ref "P5") (pin "6") (pinfunction "6_6") (pintype "passive"))
      (node (ref "P6") (pin "4") (pinfunction "4_4") (pintype "passive"))
      (node (ref "P6") (pin "5") (pinfunction "5_5") (pintype "passive"))
      (node (ref "P6") (pin "6") (pinfunction "6_6") (pintype "passive"))
      (node (ref "P9") (pin "4") (pinfunction "4_4") (pintype "passive"))
      (node (ref "P9") (pin "5") (pinfunction "5_5") (pintype "passive"))
      (node (ref "P9") (pin "6") (pinfunction "6_6") (pintype "passive"))
      (node (ref "R1") (pin "2") (pinfunction "2_2") (pintype "passive"))
      (node (ref "R14") (pin "2") (pinfunction "2_2") (pintype "passive"))
      (node (ref "R2") (pin "2") (pinfunction "2_2") (pintype "passive"))
      (node (ref "R3") (pin "2") (pinfunction "2_2") (pintype "passive"))
      (node (ref "R32") (pin "2") (pinfunction "2_2") (pintype "passive"))
      (node (ref "R9") (pin "2") (pinfunction "2_2") (pintype "passive"))
      (node (ref "SW2") (pin "3") (pinfunction "3_3") (pintype "passive"))
      (node (ref "SW2") (pin "4") (pinfunction "4_4") (pintype "passive"))
      (node (ref "TF Card 2") (pin "6") (pinfunction "6_6") (pintype "passive"))
      (node (ref "U1") (pin "2") (pinfunction "GND_2") (pintype "passive"))
      (node (ref "U2") (pin "5") (pinfunction "GND_5") (pintype "passive"))
      (node (ref "U3") (pin "4") (pinfunction "GND_4") (pintype "passive"))
      (node (ref "U4") (pin "1") (pinfunction "1_1") (pintype "passive"))
      (node (ref "U5") (pin "11") (pinfunction "VSS_OSC_11") (pintype "passive"))
      (node (ref "U5") (pin "112") (pinfunction "VSSQ_112") (pintype "passive"))
      (node (ref "U5") (pin "121") (pinfunction "VSS_121") (pintype "passive"))
      (node (ref "U5") (pin "127") (pinfunction "VSSQ_127") (pintype "passive"))
      (node (ref "U5") (pin "16") (pinfunction "VSSA_16") (pintype "passive"))
      (node (ref "U5") (pin "2") (pinfunction "VSS_2") (pintype "passive"))
      (node (ref "U5") (pin "31") (pinfunction "VSS_31") (pintype "passive"))
      (node (ref "U5") (pin "34") (pinfunction "VSSQ_34") (pintype "passive"))
      (node (ref "U5") (pin "44") (pinfunction "VSSQ_44") (pintype "passive"))
      (node (ref "U5") (pin "63") (pinfunction "VSSQ_63") (pintype "passive"))
      (node (ref "U5") (pin "66") (pinfunction "GND_66") (pintype "passive"))
      (node (ref "U5") (pin "68") (pinfunction "GND_68") (pintype "passive"))
      (node (ref "U5") (pin "69") (pinfunction "GND_69") (pintype "passive"))
      (node (ref "U5") (pin "81") (pinfunction "VSS_81") (pintype "passive"))
      (node (ref "U5") (pin "98") (pinfunction "VSSQ_98") (pintype "passive"))
      (node (ref "USB1") (pin "4") (pinfunction "GND_4") (pintype "passive"))
      (node (ref "USB1") (pin "5") (pinfunction "GND_5") (pintype "passive"))
      (node (ref "USB1") (pin "6") (pinfunction "TBD_6") (pintype "passive"))
      (node (ref "USB1") (pin "7") (pinfunction "TBD_7") (pintype "passive"))
      (node (ref "USB1") (pin "8") (pinfunction "TBD_8") (pintype "passive"))
      (node (ref "USB1") (pin "9") (pinfunction "TBD_9") (pintype "passive"))
      (node (ref "Y2") (pin "2") (pinfunction "NC_2") (pintype "passive"))
      (node (ref "Y2") (pin "4") (pinfunction "NC_4") (pintype "passive"))
    )
    (net (code "92") (name "Net-(8266-CH_PD)") (class "Default")
      (node (ref "8266") (pin "3") (pinfunction "CH_PD_3") (pintype "passive"))
      (node (ref "R31") (pin "2") (pinfunction "2_2") (pintype "passive"))
    )
    (net (code "93") (name "Net-(8266-GPIO1{slash}SPICS1{slash}TXD0)") (class "Default")
      (node (ref "8266") (pin "22") (pinfunction "GPIO1/SPICS1/TXD0_22") (pintype "passive"))
      (node (ref "R4") (pin "1") (pinfunction "1_1") (pintype "passive"))
    )
    (net (code "94") (name "Net-(8266-GPIO15{slash}HSPICS{slash}RTS0{slash}TXD2)") (class "Default")
      (node (ref "8266") (pin "16") (pinfunction "GPIO15/HSPICS/RTS0/TXD2_16") (pintype "passive"))
      (node (ref "R32") (pin "1") (pinfunction "1_1") (pintype "passive"))
    )
    (net (code "95") (name "Net-(D1-A)") (class "Default")
      (node (ref "D1") (pin "1") (pinfunction "A_1") (pintype "passive"))
      (node (ref "L1") (pin "1") (pinfunction "1_1") (pintype "passive"))
      (node (ref "U1") (pin "1") (pinfunction "SW_1") (pintype "passive"))
    )
    (net (code "96") (name "Net-(D2-Pad2)") (class "Default")
      (node (ref "D2") (pin "2") (pinfunction "2_2") (pintype "passive"))
      (node (ref "R2") (pin "1") (pinfunction "1_1") (pintype "passive"))
    )
    (net (code "97") (name "Net-(D3-Pad2)") (class "Default")
      (node (ref "D3") (pin "2") (pinfunction "2_2") (pintype "passive"))
      (node (ref "R3") (pin "1") (pinfunction "1_1") (pintype "passive"))
    )
    (net (code "98") (name "Net-(D4-Pad1)") (class "Default")
      (node (ref "D4") (pin "1") (pinfunction "1_1") (pintype "passive"))
      (node (ref "R12") (pin "2") (pinfunction "2_2") (pintype "passive"))
    )
    (net (code "99") (name "Net-(D5-Pad2)") (class "Default")
      (node (ref "D5") (pin "2") (pinfunction "2_2") (pintype "passive"))
      (node (ref "R1") (pin "1") (pinfunction "1_1") (pintype "passive"))
    )
    (net (code "100") (name "Net-(U5-OSC_IN)") (class "Default")
      (node (ref "C30") (pin "1") (pinfunction "1_1") (pintype "passive"))
      (node (ref "U5") (pin "9") (pinfunction "OSC_IN_9") (pintype "passive"))
      (node (ref "Y2") (pin "1") (pinfunction "X1_1") (pintype "passive"))
    )
    (net (code "101") (name "Net-(U5-OSC_OUT)") (class "Default")
      (node (ref "C31") (pin "1") (pinfunction "1_1") (pintype "passive"))
      (node (ref "U5") (pin "10") (pinfunction "OSC_OUT_10") (pintype "passive"))
      (node (ref "Y2") (pin "3") (pinfunction "X2_3") (pintype "passive"))
    )
    (net (code "102") (name "Net-(U5-V-CAP)") (class "Default")
      (node (ref "C32") (pin "1") (pinfunction "1_1") (pintype "passive"))
      (node (ref "U5") (pin "123") (pinfunction "V-CAP_123") (pintype "passive"))
    )
    (net (code "103") (name "VCC_IN") (class "Default")
      (node (ref "P6") (pin "3") (pinfunction "3_3") (pintype "passive"))
      (node (ref "P9") (pin "3") (pinfunction "3_3") (pintype "passive"))
      (node (ref "R26") (pin "1") (pinfunction "1_1") (pintype "passive"))
      (node (ref "R37") (pin "1") (pinfunction "1_1") (pintype "passive"))
      (node (ref "Switch_1") (pin "1") (pinfunction "A1_1") (pintype "passive"))
      (node (ref "Switch_1") (pin "4") (pinfunction "B1_4") (pintype "passive"))
      (node (ref "USB1") (pin "1") (pinfunction "VCC_1") (pintype "passive"))
    )
    (net (code "104") (name "unconnected-(8266-ADC{slash}TOUT-Pad2)") (class "Default")
      (node (ref "8266") (pin "2") (pinfunction "ADC/TOUT_2") (pintype "passive"))
    )
    (net (code "105") (name "unconnected-(8266-CS0-Pad9)") (class "Default")
      (node (ref "8266") (pin "9") (pinfunction "CS0_9") (pintype "passive"))
    )
    (net (code "106") (name "unconnected-(8266-GPIO0{slash}SPICS2-Pad18)") (class "Default")
      (node (ref "8266") (pin "18") (pinfunction "GPIO0/SPICS2_18") (pintype "passive"))
    )
    (net (code "107") (name "unconnected-(8266-GPIO2{slash}TXD1-Pad17)") (class "Default")
      (node (ref "8266") (pin "17") (pinfunction "GPIO2/TXD1_17") (pintype "passive"))
    )
    (net (code "108") (name "unconnected-(8266-GPIO4-Pad19)") (class "Default")
      (node (ref "8266") (pin "19") (pinfunction "GPIO4_19") (pintype "passive"))
    )
    (net (code "109") (name "unconnected-(8266-GPIO5-Pad20)") (class "Default")
      (node (ref "8266") (pin "20") (pinfunction "GPIO5_20") (pintype "passive"))
    )
    (net (code "110") (name "unconnected-(8266-GPIO9-Pad11)") (class "Default")
      (node (ref "8266") (pin "11") (pinfunction "GPIO9_11") (pintype "passive"))
    )
    (net (code "111") (name "unconnected-(8266-GPIO10-Pad12)") (class "Default")
      (node (ref "8266") (pin "12") (pinfunction "GPIO10_12") (pintype "passive"))
    )
    (net (code "112") (name "unconnected-(8266-GPIO12{slash}HSPI_MISO-Pad6)") (class "Default")
      (node (ref "8266") (pin "6") (pinfunction "GPIO12/HSPI_MISO_6") (pintype "passive"))
    )
    (net (code "113") (name "unconnected-(8266-GPIO13{slash}HSPI_MOSI{slash}CTS0{slash}RXD2-Pad7)") (class "Default")
      (node (ref "8266") (pin "7") (pinfunction "GPIO13/HSPI_MOSI/CTS0/RXD2_7") (pintype "passive"))
    )
    (net (code "114") (name "unconnected-(8266-GPIO14{slash}HSPI_SCK-Pad5)") (class "Default")
      (node (ref "8266") (pin "5") (pinfunction "GPIO14/HSPI_SCK_5") (pintype "passive"))
    )
    (net (code "115") (name "unconnected-(8266-GPIO16{slash}~{WAKE}-Pad4)") (class "Default")
      (node (ref "8266") (pin "4") (pinfunction "GPIO16/~{WAKE}_4") (pintype "passive"))
    )
    (net (code "116") (name "unconnected-(8266-MISO-Pad10)") (class "Default")
      (node (ref "8266") (pin "10") (pinfunction "MISO_10") (pintype "passive"))
    )
    (net (code "117") (name "unconnected-(8266-MOSI-Pad13)") (class "Default")
      (node (ref "8266") (pin "13") (pinfunction "MOSI_13") (pintype "passive"))
    )
    (net (code "118") (name "unconnected-(8266-SCLK-Pad14)") (class "Default")
      (node (ref "8266") (pin "14") (pinfunction "SCLK_14") (pintype "passive"))
    )
    (net (code "119") (name "unconnected-(LCD_3-NC-Pad1)") (class "Default")
      (node (ref "LCD_3") (pin "1") (pinfunction "NC_1") (pintype "passive+no_connect"))
    )
    (net (code "120") (name "unconnected-(LCD_3-NC-Pad2)") (class "Default")
      (node (ref "LCD_3") (pin "2") (pinfunction "NC_2") (pintype "passive+no_connect"))
    )
    (net (code "121") (name "unconnected-(LCD_3-NC-Pad3)") (class "Default")
      (node (ref "LCD_3") (pin "3") (pinfunction "NC_3") (pintype "passive+no_connect"))
    )
    (net (code "122") (name "unconnected-(LCD_3-NC-Pad4)") (class "Default")
      (node (ref "LCD_3") (pin "4") (pinfunction "NC_4") (pintype "passive+no_connect"))
    )
    (net (code "123") (name "unconnected-(LCD_3-SDO-Pad38)") (class "Default")
      (node (ref "LCD_3") (pin "38") (pinfunction "SDO_38") (pintype "passive+no_connect"))
    )
    (net (code "124") (name "unconnected-(P3-Pad7)") (class "Default")
      (node (ref "P3") (pin "7") (pinfunction "7_7") (pintype "passive"))
    )
    (net (code "125") (name "unconnected-(P3-Pad8)") (class "Default")
      (node (ref "P3") (pin "8") (pinfunction "8_8") (pintype "passive"))
    )
    (net (code "126") (name "unconnected-(TF Card 2-Pad9)") (class "Default")
      (node (ref "TF Card 2") (pin "9") (pinfunction "9_9") (pintype "passive+no_connect"))
    )
    (net (code "127") (name "unconnected-(U5-NC-Pad3)") (class "Default")
      (node (ref "U5") (pin "3") (pinfunction "NC_3") (pintype "passive+no_connect"))
    )
    (net (code "128") (name "unconnected-(U5-NC-Pad12)") (class "Default")
      (node (ref "U5") (pin "12") (pinfunction "NC_12") (pintype "passive+no_connect"))
    )
    (net (code "129") (name "unconnected-(U5-NC-Pad13)") (class "Default")
      (node (ref "U5") (pin "13") (pinfunction "NC_13") (pintype "passive+no_connect"))
    )
    (net (code "130") (name "unconnected-(U5-NC-Pad14)") (class "Default")
      (node (ref "U5") (pin "14") (pinfunction "NC_14") (pintype "passive+no_connect"))
    )
    (net (code "131") (name "unconnected-(U5-NC-Pad15)") (class "Default")
      (node (ref "U5") (pin "15") (pinfunction "NC_15") (pintype "passive+no_connect"))
    )
    (net (code "132") (name "unconnected-(U5-NC-Pad21)") (class "Default")
      (node (ref "U5") (pin "21") (pinfunction "NC_21") (pintype "passive+no_connect"))
    )
    (net (code "133") (name "unconnected-(U5-NC-Pad22)") (class "Default")
      (node (ref "U5") (pin "22") (pinfunction "NC_22") (pintype "passive+no_connect"))
    )
  )
)
